# C-03_eMMC_NAND_TF_QSPI.net
KiCad netlist of a schematic drawn in Altium Designer
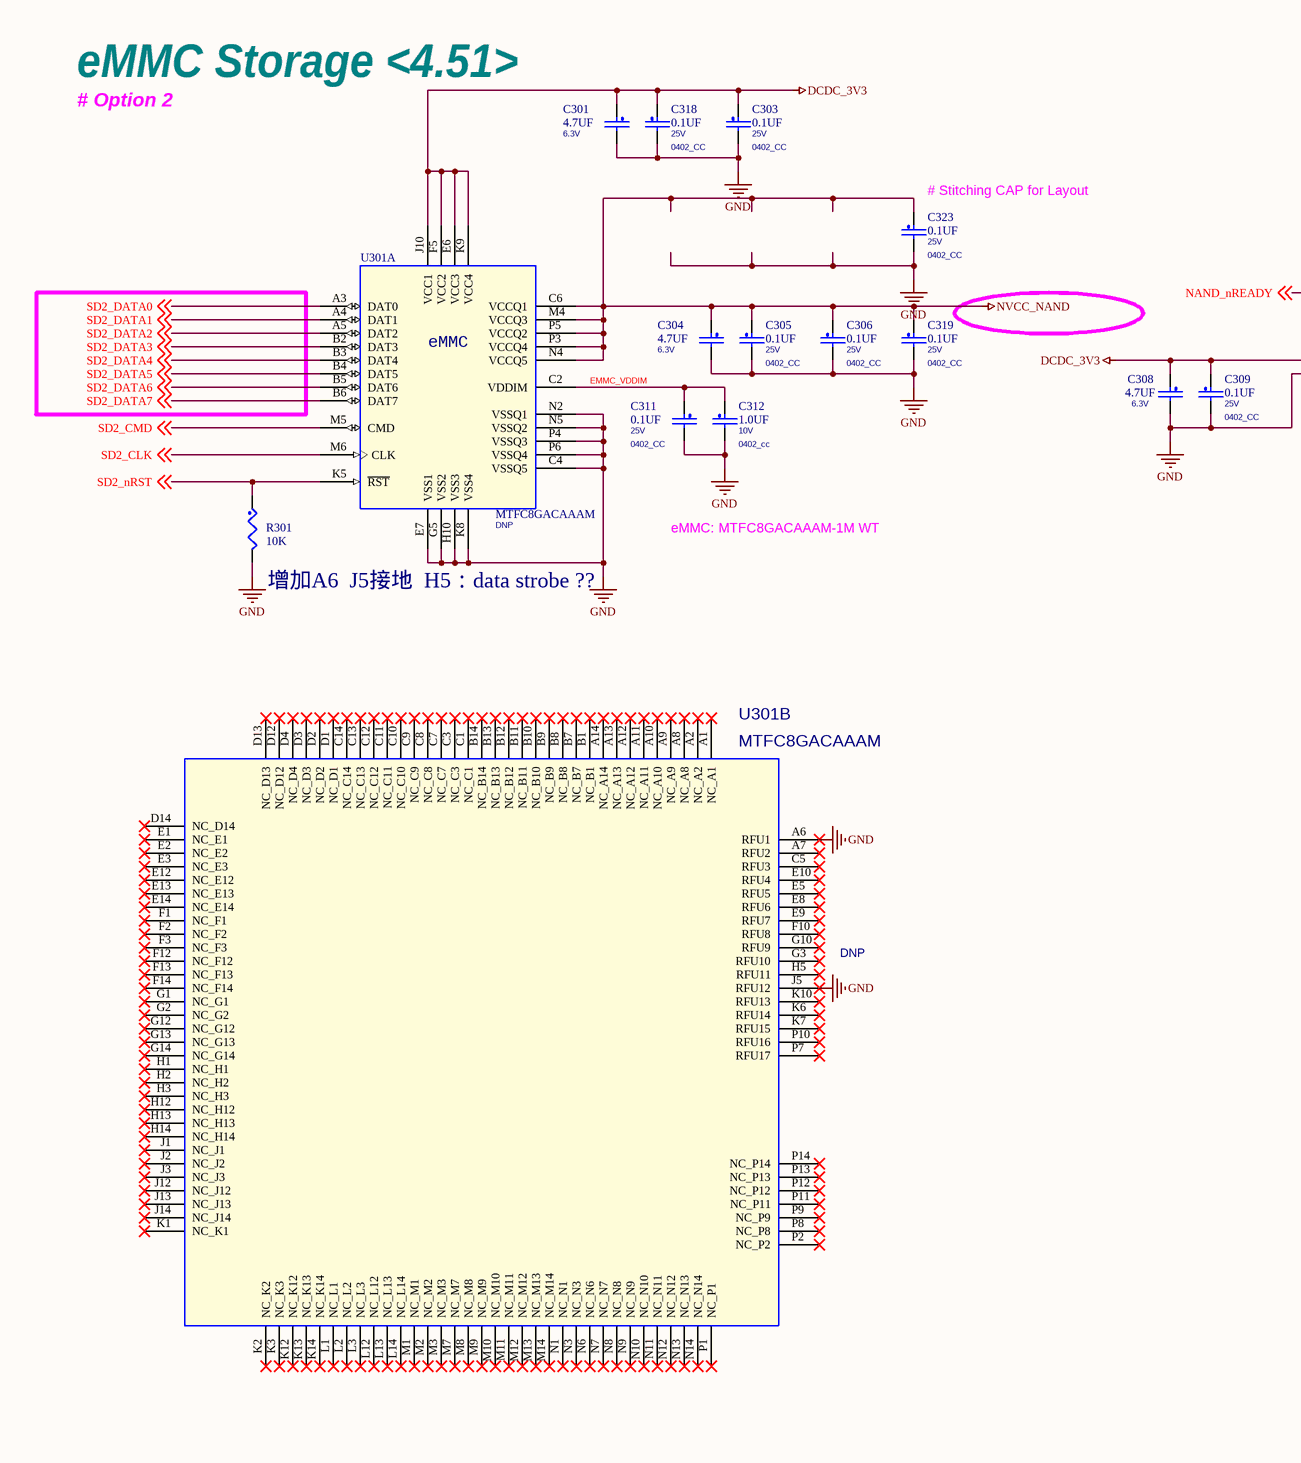
[diagram p0: C-03 eMMC_NAND_TF_QSPI.SchDoc, left]
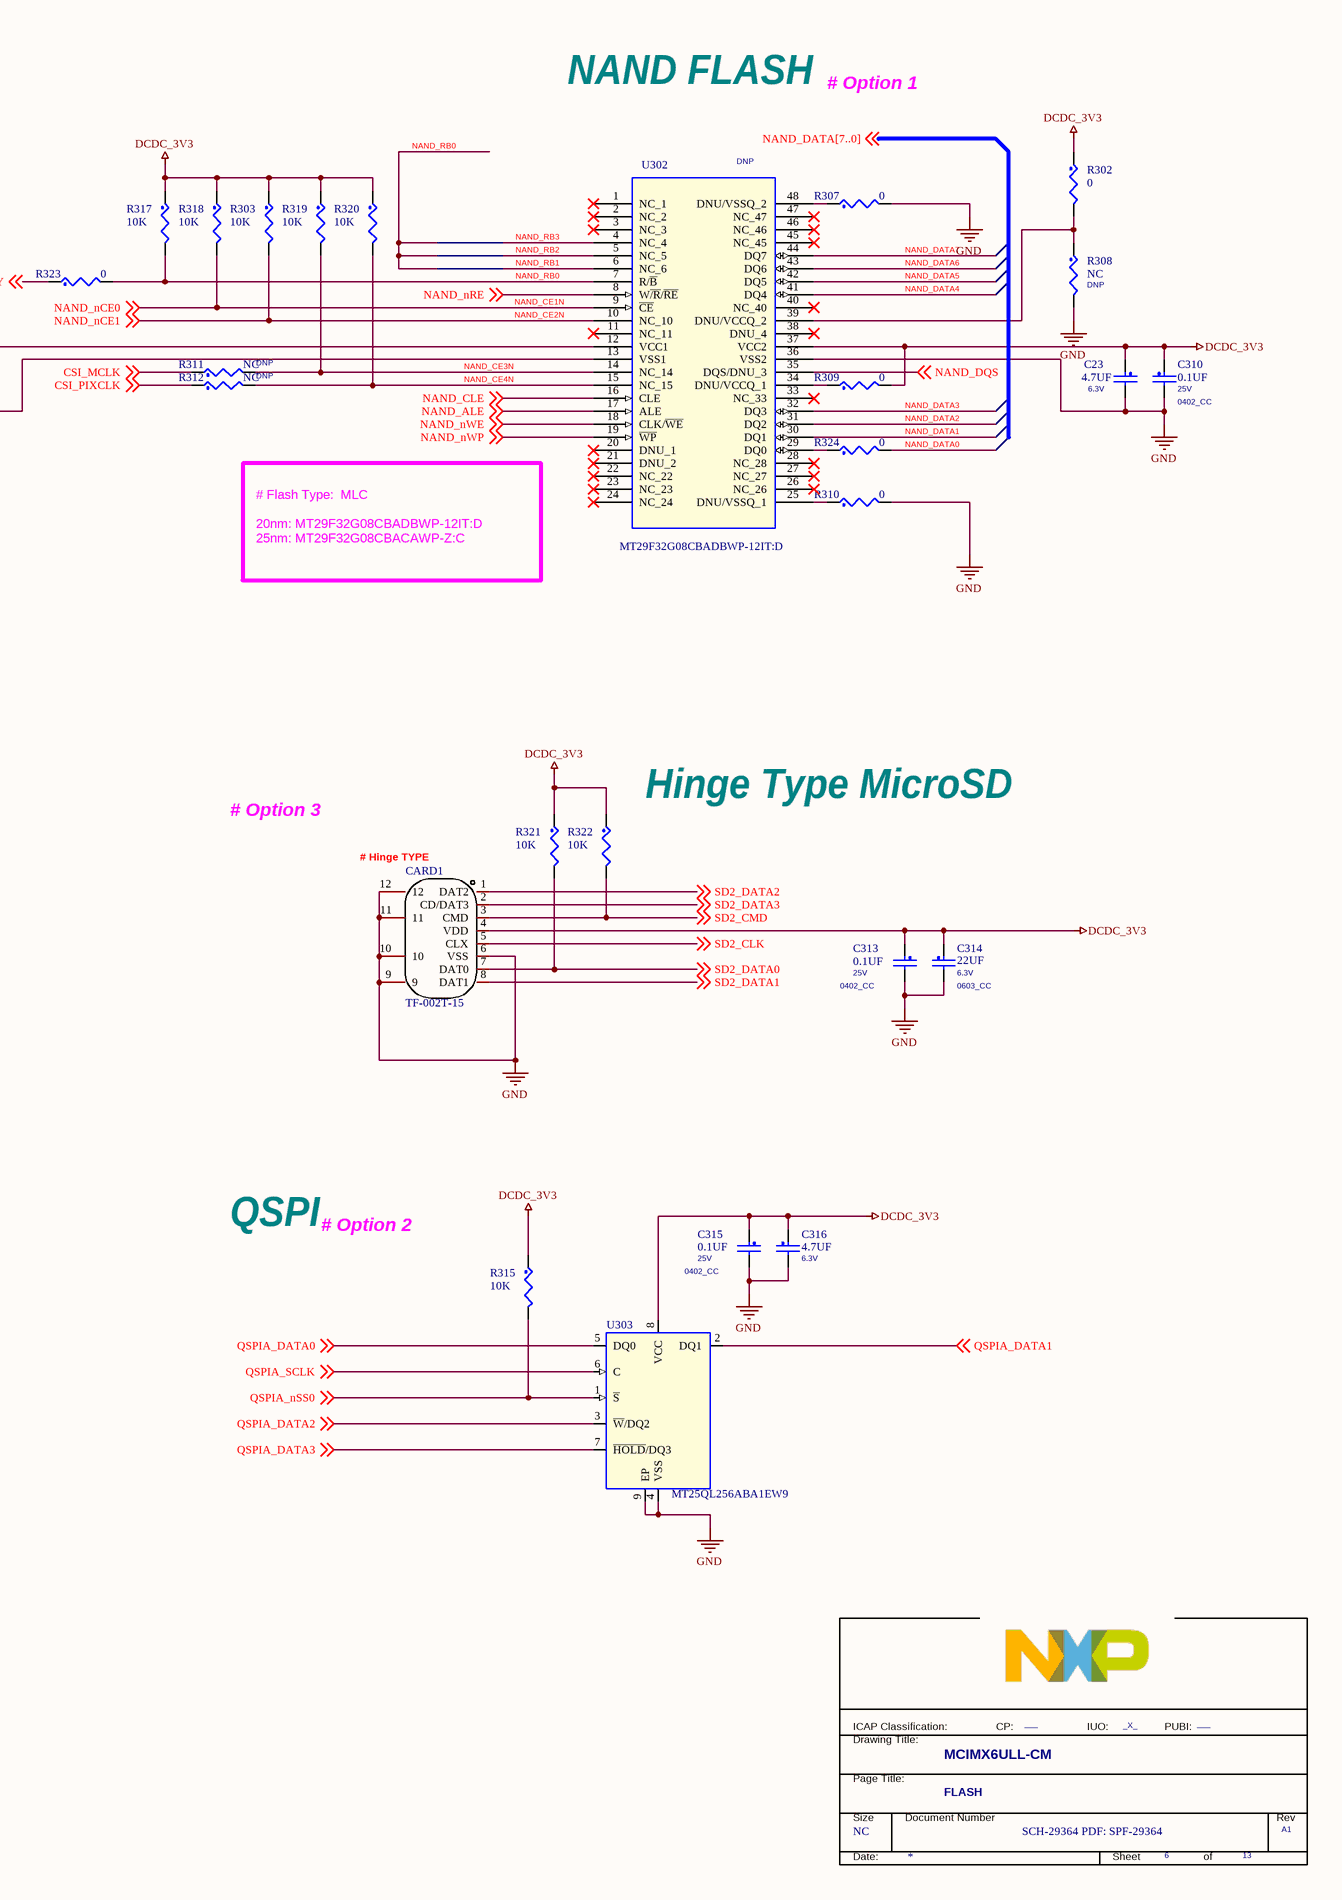
[diagram p1: C-03 eMMC_NAND_TF_QSPI.SchDoc, right]

(export (version "E")
  (design (tool "Eeschema 10.0.6"))
  (components
    (comp (ref "*")
      (value "TitleBlock_FS")
      (fields
        (field (name "PAGETITLE") "FLASH")
        (field (name "PAGE COUNT") "13")
        (field (name "PAGE NUMBER") "6")
        (field (name "PAGE SIZE") "NC")
        (field (name "TITLE") "MCIMX6ULL-CM")
        (field (name "REVCODE") "A1")
        (field (name "DOC") "SCH-29364 PDF: SPF-29364")
        (field (name "FCP") "___")
        (field (name "PUBI") "___")
        (field (name "FIUO") "_X_")
      )
      (libsource (lib "*") (part "TitleBlock_FS"))
    )
    (comp (ref "C23")
      (value "4.7UF")
      (footprint "0402T_C")
      (description "CAP CER 4.7UF 6.3V 20% X5R 0402")
      (fields
        (field (name "TOLERANCE") "20%")
        (field (name "VOLTAGE RATING") "6.3V")
        (field (name "VOLTAGE") "6.3V")
      )
      (libsource (lib "*") (part "CAP_NP"))
    )
    (comp (ref "C301")
      (value "4.7UF")
      (footprint "0402T_C")
      (description "CAP CER 4.7UF 6.3V 20% X5R 0402")
      (fields
        (field (name "TOLERANCE") "20%")
        (field (name "VOLTAGE RATING") "6.3V")
        (field (name "VOLTAGE") "6.3V")
      )
      (libsource (lib "*") (part "CAP_NP"))
    )
    (comp (ref "C303")
      (value "0.1UF")
      (footprint "0402T_C")
      (description "CAP CER 0.1UF 25V 10% X5R 0402")
      (fields
        (field (name "VOLTAGE") "25V")
        (field (name "TOLERANCE") "10%")
        (field (name "PCB FOOTPRINT") "0402_CC")
      )
      (libsource (lib "*") (part "CAP_NP"))
    )
    (comp (ref "C304")
      (value "4.7UF")
      (footprint "0402T_C")
      (description "CAP CER 4.7UF 6.3V 20% X5R 0402")
      (fields
        (field (name "VOLTAGE") "6.3V")
        (field (name "VOLTAGE RATING") "6.3V")
        (field (name "TOLERANCE") "20%")
      )
      (libsource (lib "*") (part "CAP_NP"))
    )
    (comp (ref "C305")
      (value "0.1UF")
      (footprint "0402T_C")
      (description "CAP CER 0.1UF 25V 10% X5R 0402")
      (fields
        (field (name "TOLERANCE") "10%")
        (field (name "VOLTAGE") "25V")
        (field (name "PCB FOOTPRINT") "0402_CC")
      )
      (libsource (lib "*") (part "CAP_NP"))
    )
    (comp (ref "C306")
      (value "0.1UF")
      (footprint "0402T_C")
      (description "CAP CER 0.1UF 25V 10% X5R 0402")
      (fields
        (field (name "TOLERANCE") "10%")
        (field (name "VOLTAGE") "25V")
        (field (name "PCB FOOTPRINT") "0402_CC")
      )
      (libsource (lib "*") (part "CAP_NP"))
    )
    (comp (ref "C308")
      (value "4.7UF")
      (footprint "0402T_C")
      (description "CAP CER 4.7UF 6.3V 20% X5R 0402")
      (fields
        (field (name "TOLERANCE") "20%")
        (field (name "VOLTAGE RATING") "6.3V")
        (field (name "VOLTAGE") "6.3V")
      )
      (libsource (lib "*") (part "CAP_NP"))
    )
    (comp (ref "C309")
      (value "0.1UF")
      (footprint "0402T_C")
      (description "CAP CER 0.1UF 25V 10% X5R 0402")
      (fields
        (field (name "TOLERANCE") "10%")
        (field (name "VOLTAGE") "25V")
        (field (name "PCB FOOTPRINT") "0402_CC")
      )
      (libsource (lib "*") (part "CAP_NP"))
    )
    (comp (ref "C310")
      (value "0.1UF")
      (footprint "0402T_C")
      (description "CAP CER 0.1UF 25V 10% X5R 0402")
      (fields
        (field (name "VOLTAGE") "25V")
        (field (name "TOLERANCE") "10%")
        (field (name "PCB FOOTPRINT") "0402_CC")
      )
      (libsource (lib "*") (part "CAP_NP"))
    )
    (comp (ref "C311")
      (value "0.1UF")
      (footprint "0402T_C")
      (description "CAP CER 0.1UF 25V 10% X5R 0402")
      (fields
        (field (name "TOLERANCE") "10%")
        (field (name "VOLTAGE") "25V")
        (field (name "PCB FOOTPRINT") "0402_CC")
      )
      (libsource (lib "*") (part "CAP_NP"))
    )
    (comp (ref "C312")
      (value "1.0UF")
      (footprint "0402T_C")
      (description "CAP CER 1.0UF 10V 10% X5R 0402")
      (fields (field (name "VOLTAGE") "10V") (field (name "PCB FOOTPRINT") "0402_cc"))
      (libsource (lib "*") (part "CAP_NP"))
    )
    (comp (ref "C313")
      (value "0.1UF")
      (footprint "0402T_C")
      (description "CAP CER 0.1UF 25V 10% X5R 0402")
      (fields
        (field (name "TOLERANCE") "10%")
        (field (name "VOLTAGE") "25V")
        (field (name "PCB FOOTPRINT") "0402_CC")
      )
      (libsource (lib "*") (part "CAP_NP"))
    )
    (comp (ref "C314")
      (value "22UF")
      (footprint "0603_CC")
      (description "CAP CER 22UF 6.3V 20% X5R 0603")
      (fields
        (field (name "VOLTAGE RATING") "6.3V")
        (field (name "TOLERANCE") "20%")
        (field (name "VOLTAGE") "6.3V")
        (field (name "PCB FOOTPRINT") "0603_CC")
      )
      (libsource (lib "*") (part "CAP_NP"))
    )
    (comp (ref "C315")
      (value "0.1UF")
      (footprint "0402T_C")
      (description "CAP CER 0.1UF 25V 10% X5R 0402")
      (fields
        (field (name "TOLERANCE") "10%")
        (field (name "VOLTAGE") "25V")
        (field (name "PCB FOOTPRINT") "0402_CC")
      )
      (libsource (lib "*") (part "CAP_NP"))
    )
    (comp (ref "C316")
      (value "4.7UF")
      (footprint "0402T_C")
      (description "CAP CER 4.7UF 6.3V 20% X5R 0402")
      (fields
        (field (name "TOLERANCE") "20%")
        (field (name "VOLTAGE RATING") "6.3V")
        (field (name "VOLTAGE") "6.3V")
      )
      (libsource (lib "*") (part "CAP_NP"))
    )
    (comp (ref "C318")
      (value "0.1UF")
      (footprint "0402T_C")
      (description "CAP CER 0.1UF 25V 10% X5R 0402")
      (fields
        (field (name "TOLERANCE") "10%")
        (field (name "VOLTAGE") "25V")
        (field (name "PCB FOOTPRINT") "0402_CC")
      )
      (libsource (lib "*") (part "CAP_NP"))
    )
    (comp (ref "C319")
      (value "0.1UF")
      (footprint "0402T_C")
      (description "CAP CER 0.1UF 25V 10% X5R 0402")
      (fields
        (field (name "VOLTAGE") "25V")
        (field (name "TOLERANCE") "10%")
        (field (name "PCB FOOTPRINT") "0402_CC")
      )
      (libsource (lib "*") (part "CAP_NP"))
    )
    (comp (ref "C323")
      (value "0.1UF")
      (footprint "0402T_C")
      (description "CAP CER 0.1UF 25V 10% X5R 0402")
      (fields
        (field (name "TOLERANCE") "10%")
        (field (name "VOLTAGE") "25V")
        (field (name "PCB FOOTPRINT") "0402_CC")
      )
      (libsource (lib "*") (part "CAP_NP"))
    )
    (comp (ref "CARD1")
      (value "TF-002T-15")
      (footprint "TF-SMD_TF-002T-15")
      (description "卡连接方式:翻盖式;卡类型:MicroSD卡(TF卡);连接器类型:卡座;本体最大高度:-;触头材质:-;触头镀层:-;工作温度范围:-;焊接温度(最大值):-;")
      (fields (field (name "NAME") "TF-002T-15") (field (name "MANUFACTURER") "SOFNG(硕方)"))
      (libsource (lib "altium-import") (part "root_0_mirrored_TF-002T-15_"))
    )
    (comp (ref "R301")
      (value "10K")
      (footprint "0402T_C")
      (description "RES MF 10K 1/16W 5% 0402")
      (fields (field (name "TOLERANCE") "5%"))
      (libsource (lib "*") (part "RES"))
    )
    (comp (ref "R302")
      (value "0")
      (footprint "0402T_C")
      (description "RES MF ZERO OHM 1/16W 5% 0402")
      (fields (field (name "TOLERANCE") "5%"))
      (libsource (lib "*") (part "RES"))
    )
    (comp (ref "R303")
      (value "10K")
      (footprint "0402T_C")
      (description "RES MF 10K 1/16W 5% 0402")
      (fields (field (name "TOLERANCE") "5%"))
      (libsource (lib "*") (part "RES"))
    )
    (comp (ref "R307")
      (value "0")
      (footprint "0402T_C")
      (description "RES MF ZERO OHM 1/16W 5% 0402")
      (fields (field (name "TOLERANCE") "5%"))
      (libsource (lib "*") (part "RES"))
    )
    (comp (ref "R308")
      (value "NC")
      (footprint "0402T_C")
      (description "RES MF ZERO OHM 1/16W 5% 0402")
      (fields (field (name "ASSY_OPT") "DNP") (field (name "TOLERANCE") "5%"))
      (libsource (lib "*") (part "RES"))
    )
    (comp (ref "R309")
      (value "0")
      (footprint "0402T_C")
      (description "RES MF ZERO OHM 1/16W 5% 0402")
      (fields (field (name "TOLERANCE") "5%"))
      (libsource (lib "*") (part "RES"))
    )
    (comp (ref "R310")
      (value "0")
      (footprint "0402T_C")
      (description "RES MF ZERO OHM 1/16W 5% 0402")
      (fields (field (name "TOLERANCE") "5%"))
      (libsource (lib "*") (part "RES"))
    )
    (comp (ref "R311")
      (value "NC")
      (footprint "0402T_C")
      (description "RES MF ZERO OHM 1/16W 5% 0402")
      (fields (field (name "ASSY_OPT") "DNP") (field (name "TOLERANCE") "5%"))
      (libsource (lib "*") (part "RES"))
    )
    (comp (ref "R312")
      (value "NC")
      (footprint "0402T_C")
      (description "RES MF ZERO OHM 1/16W 5% 0402")
      (fields (field (name "ASSY_OPT") "DNP") (field (name "TOLERANCE") "5%"))
      (libsource (lib "*") (part "RES"))
    )
    (comp (ref "R315")
      (value "10K")
      (footprint "0402T_C")
      (description "RES MF 10K 1/16W 5% 0402")
      (fields (field (name "TOLERANCE") "5%"))
      (libsource (lib "*") (part "RES"))
    )
    (comp (ref "R317")
      (value "10K")
      (footprint "0402T_C")
      (description "RES MF 10K 1/16W 5% 0402")
      (fields (field (name "TOLERANCE") "5%"))
      (libsource (lib "*") (part "RES"))
    )
    (comp (ref "R318")
      (value "10K")
      (footprint "0402T_C")
      (description "RES MF 10K 1/16W 5% 0402")
      (fields (field (name "TOLERANCE") "5%"))
      (libsource (lib "*") (part "RES"))
    )
    (comp (ref "R319")
      (value "10K")
      (footprint "0402T_C")
      (description "RES MF 10K 1/16W 5% 0402")
      (fields (field (name "TOLERANCE") "5%"))
      (libsource (lib "*") (part "RES"))
    )
    (comp (ref "R320")
      (value "10K")
      (footprint "0402T_C")
      (description "RES MF 10K 1/16W 5% 0402")
      (fields (field (name "TOLERANCE") "5%"))
      (libsource (lib "*") (part "RES"))
    )
    (comp (ref "R321")
      (value "10K")
      (footprint "0402T_C")
      (description "RES MF 10K 1/16W 5% 0402")
      (fields (field (name "TOLERANCE") "5%"))
      (libsource (lib "*") (part "RES"))
    )
    (comp (ref "R322")
      (value "10K")
      (footprint "0402T_C")
      (description "RES MF 10K 1/16W 5% 0402")
      (fields (field (name "TOLERANCE") "5%"))
      (libsource (lib "*") (part "RES"))
    )
    (comp (ref "R323")
      (value "0")
      (footprint "0402T_C")
      (description "RES MF ZERO OHM 1/16W 5% 0402")
      (fields (field (name "TOLERANCE") "5%"))
      (libsource (lib "*") (part "RES"))
    )
    (comp (ref "R324")
      (value "0")
      (footprint "0402T_C")
      (description "RES MF ZERO OHM 1/16W 5% 0402")
      (fields (field (name "TOLERANCE") "5%"))
      (libsource (lib "*") (part "RES"))
    )
    (comp (ref "U301")
      (value "MTFC8GACAAAM")
      (footprint "FBGA153_0P5_11P5X13")
      (description "IC MEM NAND FLASH 8GB MMC 4.51 CTLR 2.7-3.6V FBGA153")
      (fields (field (name "ASSY_OPT") "DNP"))
      (libsource (lib "*") (part "MTFC4GMVEA_WFBGA_153P"))
    )
    (comp (ref "U302")
      (value "MT29F32G08CBADBWP-12IT:D")
      (footprint "tsop48_12x20")
      (description "IC MEM NAND FLASH ASYNC 32GB 2.7-3.6V TSOP48")
      (fields (field (name "ASSY_OPT") "DNP"))
      (libsource (lib "*") (part "MT29F32G08CBADB_48P"))
    )
    (comp (ref "U303")
      (value "MT25QL256ABA1EW9")
      (footprint "mlp8_1p27_8x6")
      (description "IC MEM FLASH SERIAL NOR 256MBIT 2.7-3.6V MLP8")
      (libsource (lib "*") (part "MT25QL256ABA1EW9_9P"))
    )
  )
  (nets
    (net (code "1") (name "/EMMC_VDDIM") (class "Default")
      (node (ref "C311") (pin "1") (pinfunction "1_1") (pintype "passive"))
      (node (ref "C312") (pin "1") (pinfunction "1_1") (pintype "passive"))
      (node (ref "U301") (pin "C2") (pinfunction "VDDIM_C2") (pintype "power_in"))
    )
    (net (code "2") (name "/NAND_CE3N") (class "Default")
      (node (ref "R311") (pin "2") (pinfunction "2_2") (pintype "passive"))
      (node (ref "R319") (pin "2") (pinfunction "2_2") (pintype "passive"))
      (node (ref "U302") (pin "14") (pinfunction "NC_14_14") (pintype "passive"))
    )
    (net (code "3") (name "/NAND_CE4N") (class "Default")
      (node (ref "R312") (pin "2") (pinfunction "2_2") (pintype "passive"))
      (node (ref "R320") (pin "2") (pinfunction "2_2") (pintype "passive"))
      (node (ref "U302") (pin "15") (pinfunction "NC_15_15") (pintype "passive"))
    )
    (net (code "4") (name "/NAND_RB0") (class "Default")
      (node (ref "R317") (pin "2") (pinfunction "2_2") (pintype "passive"))
      (node (ref "R323") (pin "2") (pinfunction "2_2") (pintype "passive"))
      (node (ref "U302") (pin "4") (pinfunction "NC_4_4") (pintype "passive"))
      (node (ref "U302") (pin "5") (pinfunction "NC_5_5") (pintype "passive"))
      (node (ref "U302") (pin "6") (pinfunction "NC_6_6") (pintype "passive"))
      (node (ref "U302") (pin "7") (pinfunction "R/~{B}_7") (pintype "open_collector"))
    )
    (net (code "5") (name "CSI_MCLK") (class "Default")
      (node (ref "R311") (pin "1") (pinfunction "1_1") (pintype "passive"))
    )
    (net (code "6") (name "CSI_PIXCLK") (class "Default")
      (node (ref "R312") (pin "1") (pinfunction "1_1") (pintype "passive"))
    )
    (net (code "7") (name "DCDC_3V3") (class "Default")
      (node (ref "C23") (pin "1") (pinfunction "1_1") (pintype "passive"))
      (node (ref "C301") (pin "1") (pinfunction "1_1") (pintype "passive"))
      (node (ref "C303") (pin "1") (pinfunction "1_1") (pintype "passive"))
      (node (ref "C308") (pin "1") (pinfunction "1_1") (pintype "passive"))
      (node (ref "C309") (pin "1") (pinfunction "1_1") (pintype "passive"))
      (node (ref "C310") (pin "1") (pinfunction "1_1") (pintype "passive"))
      (node (ref "C313") (pin "1") (pinfunction "1_1") (pintype "passive"))
      (node (ref "C314") (pin "1") (pinfunction "1_1") (pintype "passive"))
      (node (ref "C315") (pin "1") (pinfunction "1_1") (pintype "passive"))
      (node (ref "C316") (pin "1") (pinfunction "1_1") (pintype "passive"))
      (node (ref "C318") (pin "1") (pinfunction "1_1") (pintype "passive"))
      (node (ref "CARD1") (pin "4") (pinfunction "VDD_4") (pintype "passive"))
      (node (ref "R302") (pin "1") (pinfunction "1_1") (pintype "passive"))
      (node (ref "R303") (pin "1") (pinfunction "1_1") (pintype "passive"))
      (node (ref "R309") (pin "2") (pinfunction "2_2") (pintype "passive"))
      (node (ref "R315") (pin "1") (pinfunction "1_1") (pintype "passive"))
      (node (ref "R317") (pin "1") (pinfunction "1_1") (pintype "passive"))
      (node (ref "R318") (pin "1") (pinfunction "1_1") (pintype "passive"))
      (node (ref "R319") (pin "1") (pinfunction "1_1") (pintype "passive"))
      (node (ref "R320") (pin "1") (pinfunction "1_1") (pintype "passive"))
      (node (ref "R321") (pin "1") (pinfunction "1_1") (pintype "passive"))
      (node (ref "R322") (pin "1") (pinfunction "1_1") (pintype "passive"))
      (node (ref "U301") (pin "E6") (pinfunction "VCC3_E6") (pintype "power_in"))
      (node (ref "U301") (pin "F5") (pinfunction "VCC2_F5") (pintype "power_in"))
      (node (ref "U301") (pin "J10") (pinfunction "VCC1_J10") (pintype "power_in"))
      (node (ref "U301") (pin "K9") (pinfunction "VCC4_K9") (pintype "power_in"))
      (node (ref "U302") (pin "12") (pinfunction "VCC1_12") (pintype "power_in"))
      (node (ref "U302") (pin "37") (pinfunction "VCC2_37") (pintype "power_in"))
      (node (ref "U303") (pin "8") (pinfunction "VCC_8") (pintype "power_in"))
    )
    (net (code "8") (name "GND") (class "Default")
      (node (ref "C23") (pin "2") (pinfunction "2_2") (pintype "passive"))
      (node (ref "C301") (pin "2") (pinfunction "2_2") (pintype "passive"))
      (node (ref "C303") (pin "2") (pinfunction "2_2") (pintype "passive"))
      (node (ref "C304") (pin "2") (pinfunction "2_2") (pintype "passive"))
      (node (ref "C305") (pin "2") (pinfunction "2_2") (pintype "passive"))
      (node (ref "C306") (pin "2") (pinfunction "2_2") (pintype "passive"))
      (node (ref "C308") (pin "2") (pinfunction "2_2") (pintype "passive"))
      (node (ref "C309") (pin "2") (pinfunction "2_2") (pintype "passive"))
      (node (ref "C310") (pin "2") (pinfunction "2_2") (pintype "passive"))
      (node (ref "C311") (pin "2") (pinfunction "2_2") (pintype "passive"))
      (node (ref "C312") (pin "2") (pinfunction "2_2") (pintype "passive"))
      (node (ref "C313") (pin "2") (pinfunction "2_2") (pintype "passive"))
      (node (ref "C314") (pin "2") (pinfunction "2_2") (pintype "passive"))
      (node (ref "C315") (pin "2") (pinfunction "2_2") (pintype "passive"))
      (node (ref "C316") (pin "2") (pinfunction "2_2") (pintype "passive"))
      (node (ref "C318") (pin "2") (pinfunction "2_2") (pintype "passive"))
      (node (ref "C319") (pin "2") (pinfunction "2_2") (pintype "passive"))
      (node (ref "C323") (pin "2") (pinfunction "2_2") (pintype "passive"))
      (node (ref "CARD1") (pin "10") (pinfunction "10_10") (pintype "passive"))
      (node (ref "CARD1") (pin "11") (pinfunction "11_11") (pintype "passive"))
      (node (ref "CARD1") (pin "12") (pinfunction "12_12") (pintype "passive"))
      (node (ref "CARD1") (pin "6") (pinfunction "VSS_6") (pintype "passive"))
      (node (ref "CARD1") (pin "9") (pinfunction "9_9") (pintype "passive"))
      (node (ref "R301") (pin "2") (pinfunction "2_2") (pintype "passive"))
      (node (ref "R307") (pin "2") (pinfunction "2_2") (pintype "passive"))
      (node (ref "R308") (pin "2") (pinfunction "2_2") (pintype "passive"))
      (node (ref "R310") (pin "2") (pinfunction "2_2") (pintype "passive"))
      (node (ref "U301") (pin "A6") (pinfunction "RFU1_A6") (pintype "passive"))
      (node (ref "U301") (pin "C4") (pinfunction "VSSQ5_C4") (pintype "power_in"))
      (node (ref "U301") (pin "E7") (pinfunction "VSS1_E7") (pintype "power_in"))
      (node (ref "U301") (pin "G5") (pinfunction "VSS2_G5") (pintype "power_in"))
      (node (ref "U301") (pin "H10") (pinfunction "VSS3_H10") (pintype "power_in"))
      (node (ref "U301") (pin "J5") (pinfunction "RFU12_J5") (pintype "passive"))
      (node (ref "U301") (pin "K8") (pinfunction "VSS4_K8") (pintype "power_in"))
      (node (ref "U301") (pin "N2") (pinfunction "VSSQ1_N2") (pintype "power_in"))
      (node (ref "U301") (pin "N5") (pinfunction "VSSQ2_N5") (pintype "power_in"))
      (node (ref "U301") (pin "P4") (pinfunction "VSSQ3_P4") (pintype "power_in"))
      (node (ref "U301") (pin "P6") (pinfunction "VSSQ4_P6") (pintype "power_in"))
      (node (ref "U302") (pin "13") (pinfunction "VSS1_13") (pintype "power_in"))
      (node (ref "U302") (pin "36") (pinfunction "VSS2_36") (pintype "power_in"))
      (node (ref "U303") (pin "4") (pinfunction "VSS_4") (pintype "power_in"))
      (node (ref "U303") (pin "9") (pinfunction "EP_9") (pintype "power_in"))
    )
    (net (code "9") (name "NAND_ALE") (class "Default")
      (node (ref "U302") (pin "17") (pinfunction "ALE_17") (pintype "input"))
    )
    (net (code "10") (name "NAND_CLE") (class "Default")
      (node (ref "U302") (pin "16") (pinfunction "CLE_16") (pintype "input"))
    )
    (net (code "11") (name "NAND_DATA0") (class "Default")
      (node (ref "R324") (pin "2") (pinfunction "2_2") (pintype "passive"))
    )
    (net (code "12") (name "NAND_DATA1") (class "Default")
      (node (ref "U302") (pin "30") (pinfunction "DQ1_30") (pintype "bidirectional"))
    )
    (net (code "13") (name "NAND_DATA2") (class "Default")
      (node (ref "U302") (pin "31") (pinfunction "DQ2_31") (pintype "bidirectional"))
    )
    (net (code "14") (name "NAND_DATA3") (class "Default")
      (node (ref "U302") (pin "32") (pinfunction "DQ3_32") (pintype "bidirectional"))
    )
    (net (code "15") (name "NAND_DATA4") (class "Default")
      (node (ref "U302") (pin "41") (pinfunction "DQ4_41") (pintype "bidirectional"))
    )
    (net (code "16") (name "NAND_DATA5") (class "Default")
      (node (ref "U302") (pin "42") (pinfunction "DQ5_42") (pintype "bidirectional"))
    )
    (net (code "17") (name "NAND_DATA6") (class "Default")
      (node (ref "U302") (pin "43") (pinfunction "DQ6_43") (pintype "bidirectional"))
    )
    (net (code "18") (name "NAND_DATA7") (class "Default")
      (node (ref "U302") (pin "44") (pinfunction "DQ7_44") (pintype "bidirectional"))
    )
    (net (code "20") (name "NAND_DQS") (class "Default")
      (node (ref "U302") (pin "35") (pinfunction "DQS/DNU_3_35") (pintype "passive"))
    )
    (net (code "21") (name "NAND_nCE0") (class "Default")
      (node (ref "R318") (pin "2") (pinfunction "2_2") (pintype "passive"))
      (node (ref "U302") (pin "9") (pinfunction "~{CE}_9") (pintype "input"))
    )
    (net (code "22") (name "NAND_nCE1") (class "Default")
      (node (ref "R303") (pin "2") (pinfunction "2_2") (pintype "passive"))
      (node (ref "U302") (pin "10") (pinfunction "NC_10_10") (pintype "passive"))
    )
    (net (code "23") (name "NAND_nRE") (class "Default")
      (node (ref "U302") (pin "8") (pinfunction "W~{/R}/~{RE}_8") (pintype "input"))
    )
    (net (code "24") (name "NAND_nREADY") (class "Default")
      (node (ref "R323") (pin "1") (pinfunction "1_1") (pintype "passive"))
    )
    (net (code "25") (name "NAND_nWE") (class "Default")
      (node (ref "U302") (pin "18") (pinfunction "CLK/~{WE}_18") (pintype "input"))
    )
    (net (code "26") (name "NAND_nWP") (class "Default")
      (node (ref "U302") (pin "19") (pinfunction "~{WP}_19") (pintype "input"))
    )
    (net (code "27") (name "NVCC_NAND") (class "Default")
      (node (ref "C304") (pin "1") (pinfunction "1_1") (pintype "passive"))
      (node (ref "C305") (pin "1") (pinfunction "1_1") (pintype "passive"))
      (node (ref "C306") (pin "1") (pinfunction "1_1") (pintype "passive"))
      (node (ref "C319") (pin "1") (pinfunction "1_1") (pintype "passive"))
      (node (ref "C323") (pin "1") (pinfunction "1_1") (pintype "passive"))
      (node (ref "U301") (pin "C6") (pinfunction "VCCQ1_C6") (pintype "power_in"))
      (node (ref "U301") (pin "M4") (pinfunction "VCCQ3_M4") (pintype "power_in"))
      (node (ref "U301") (pin "N4") (pinfunction "VCCQ5_N4") (pintype "power_in"))
      (node (ref "U301") (pin "P3") (pinfunction "VCCQ4_P3") (pintype "power_in"))
      (node (ref "U301") (pin "P5") (pinfunction "VCCQ2_P5") (pintype "power_in"))
    )
    (net (code "28") (name "Net-(U302-DNU{slash}VCCQ_1)") (class "Default")
      (node (ref "R309") (pin "1") (pinfunction "1_1") (pintype "passive"))
      (node (ref "U302") (pin "34") (pinfunction "DNU/VCCQ_1_34") (pintype "power_in"))
    )
    (net (code "29") (name "Net-(U302-DNU{slash}VCCQ_2)") (class "Default")
      (node (ref "R302") (pin "2") (pinfunction "2_2") (pintype "passive"))
      (node (ref "R308") (pin "1") (pinfunction "1_1") (pintype "passive"))
      (node (ref "U302") (pin "39") (pinfunction "DNU/VCCQ_2_39") (pintype "passive"))
    )
    (net (code "30") (name "Net-(U302-DNU{slash}VSSQ_1)") (class "Default")
      (node (ref "R310") (pin "1") (pinfunction "1_1") (pintype "passive"))
      (node (ref "U302") (pin "25") (pinfunction "DNU/VSSQ_1_25") (pintype "power_in"))
    )
    (net (code "31") (name "Net-(U302-DNU{slash}VSSQ_2)") (class "Default")
      (node (ref "R307") (pin "1") (pinfunction "1_1") (pintype "passive"))
      (node (ref "U302") (pin "48") (pinfunction "DNU/VSSQ_2_48") (pintype "power_in"))
    )
    (net (code "32") (name "Net-(U302-DQ0)") (class "Default")
      (node (ref "R324") (pin "1") (pinfunction "1_1") (pintype "passive"))
      (node (ref "U302") (pin "29") (pinfunction "DQ0_29") (pintype "bidirectional"))
    )
    (net (code "33") (name "QSPIA_DATA0") (class "Default")
      (node (ref "U303") (pin "5") (pinfunction "DQ0_5") (pintype "bidirectional"))
    )
    (net (code "34") (name "QSPIA_DATA1") (class "Default")
      (node (ref "U303") (pin "2") (pinfunction "DQ1_2") (pintype "bidirectional"))
    )
    (net (code "35") (name "QSPIA_DATA2") (class "Default")
      (node (ref "U303") (pin "3") (pinfunction "~{W}/DQ2_3") (pintype "bidirectional"))
    )
    (net (code "36") (name "QSPIA_DATA3") (class "Default")
      (node (ref "U303") (pin "7") (pinfunction "~{HOLD}/DQ3_7") (pintype "bidirectional"))
    )
    (net (code "37") (name "QSPIA_SCLK") (class "Default")
      (node (ref "U303") (pin "6") (pinfunction "C_6") (pintype "input"))
    )
    (net (code "38") (name "QSPIA_nSS0") (class "Default")
      (node (ref "R315") (pin "2") (pinfunction "2_2") (pintype "passive"))
      (node (ref "U303") (pin "1") (pinfunction "~{S}_1") (pintype "input"))
    )
    (net (code "39") (name "SD2_CLK") (class "Default")
      (node (ref "CARD1") (pin "5") (pinfunction "CLX_5") (pintype "passive"))
      (node (ref "U301") (pin "M6") (pinfunction "CLK_M6") (pintype "input"))
    )
    (net (code "40") (name "SD2_CMD") (class "Default")
      (node (ref "CARD1") (pin "3") (pinfunction "CMD_3") (pintype "passive"))
      (node (ref "R322") (pin "2") (pinfunction "2_2") (pintype "passive"))
      (node (ref "U301") (pin "M5") (pinfunction "CMD_M5") (pintype "bidirectional"))
    )
    (net (code "41") (name "SD2_DATA0") (class "Default")
      (node (ref "CARD1") (pin "7") (pinfunction "DAT0_7") (pintype "passive"))
      (node (ref "R321") (pin "2") (pinfunction "2_2") (pintype "passive"))
      (node (ref "U301") (pin "A3") (pinfunction "DAT0_A3") (pintype "bidirectional"))
    )
    (net (code "42") (name "SD2_DATA1") (class "Default")
      (node (ref "CARD1") (pin "8") (pinfunction "DAT1_8") (pintype "passive"))
      (node (ref "U301") (pin "A4") (pinfunction "DAT1_A4") (pintype "bidirectional"))
    )
    (net (code "43") (name "SD2_DATA2") (class "Default")
      (node (ref "CARD1") (pin "1") (pinfunction "DAT2_1") (pintype "passive"))
      (node (ref "U301") (pin "A5") (pinfunction "DAT2_A5") (pintype "bidirectional"))
    )
    (net (code "44") (name "SD2_DATA3") (class "Default")
      (node (ref "CARD1") (pin "2") (pinfunction "CD/DAT3_2") (pintype "passive"))
      (node (ref "U301") (pin "B2") (pinfunction "DAT3_B2") (pintype "bidirectional"))
    )
    (net (code "45") (name "SD2_DATA4") (class "Default")
      (node (ref "U301") (pin "B3") (pinfunction "DAT4_B3") (pintype "bidirectional"))
    )
    (net (code "46") (name "SD2_DATA5") (class "Default")
      (node (ref "U301") (pin "B4") (pinfunction "DAT5_B4") (pintype "bidirectional"))
    )
    (net (code "47") (name "SD2_DATA6") (class "Default")
      (node (ref "U301") (pin "B5") (pinfunction "DAT6_B5") (pintype "bidirectional"))
    )
    (net (code "48") (name "SD2_DATA7") (class "Default")
      (node (ref "U301") (pin "B6") (pinfunction "DAT7_B6") (pintype "bidirectional"))
    )
    (net (code "49") (name "SD2_nRST") (class "Default")
      (node (ref "R301") (pin "1") (pinfunction "1_1") (pintype "passive"))
      (node (ref "U301") (pin "K5") (pinfunction "~{RST}_K5") (pintype "input"))
    )
    (net (code "50") (name "unconnected-(U301B-NC_A1-PadA1)") (class "Default")
      (node (ref "U301") (pin "A1") (pinfunction "NC_A1_A1") (pintype "passive+no_connect"))
    )
    (net (code "51") (name "unconnected-(U301B-NC_A2-PadA2)") (class "Default")
      (node (ref "U301") (pin "A2") (pinfunction "NC_A2_A2") (pintype "passive+no_connect"))
    )
    (net (code "52") (name "unconnected-(U301B-NC_A8-PadA8)") (class "Default")
      (node (ref "U301") (pin "A8") (pinfunction "NC_A8_A8") (pintype "passive+no_connect"))
    )
    (net (code "53") (name "unconnected-(U301B-NC_A9-PadA9)") (class "Default")
      (node (ref "U301") (pin "A9") (pinfunction "NC_A9_A9") (pintype "passive+no_connect"))
    )
    (net (code "54") (name "unconnected-(U301B-NC_A10-PadA10)") (class "Default")
      (node (ref "U301") (pin "A10") (pinfunction "NC_A10_A10") (pintype "passive+no_connect"))
    )
    (net (code "55") (name "unconnected-(U301B-NC_A11-PadA11)") (class "Default")
      (node (ref "U301") (pin "A11") (pinfunction "NC_A11_A11") (pintype "passive+no_connect"))
    )
    (net (code "56") (name "unconnected-(U301B-NC_A12-PadA12)") (class "Default")
      (node (ref "U301") (pin "A12") (pinfunction "NC_A12_A12") (pintype "passive+no_connect"))
    )
    (net (code "57") (name "unconnected-(U301B-NC_A13-PadA13)") (class "Default")
      (node (ref "U301") (pin "A13") (pinfunction "NC_A13_A13") (pintype "passive+no_connect"))
    )
    (net (code "58") (name "unconnected-(U301B-NC_A14-PadA14)") (class "Default")
      (node (ref "U301") (pin "A14") (pinfunction "NC_A14_A14") (pintype "passive+no_connect"))
    )
    (net (code "59") (name "unconnected-(U301B-NC_B1-PadB1)") (class "Default")
      (node (ref "U301") (pin "B1") (pinfunction "NC_B1_B1") (pintype "passive+no_connect"))
    )
    (net (code "60") (name "unconnected-(U301B-NC_B7-PadB7)") (class "Default")
      (node (ref "U301") (pin "B7") (pinfunction "NC_B7_B7") (pintype "passive+no_connect"))
    )
    (net (code "61") (name "unconnected-(U301B-NC_B8-PadB8)") (class "Default")
      (node (ref "U301") (pin "B8") (pinfunction "NC_B8_B8") (pintype "passive+no_connect"))
    )
    (net (code "62") (name "unconnected-(U301B-NC_B9-PadB9)") (class "Default")
      (node (ref "U301") (pin "B9") (pinfunction "NC_B9_B9") (pintype "passive+no_connect"))
    )
    (net (code "63") (name "unconnected-(U301B-NC_B10-PadB10)") (class "Default")
      (node (ref "U301") (pin "B10") (pinfunction "NC_B10_B10") (pintype "passive+no_connect"))
    )
    (net (code "64") (name "unconnected-(U301B-NC_B11-PadB11)") (class "Default")
      (node (ref "U301") (pin "B11") (pinfunction "NC_B11_B11") (pintype "passive+no_connect"))
    )
    (net (code "65") (name "unconnected-(U301B-NC_B12-PadB12)") (class "Default")
      (node (ref "U301") (pin "B12") (pinfunction "NC_B12_B12") (pintype "passive+no_connect"))
    )
    (net (code "66") (name "unconnected-(U301B-NC_B13-PadB13)") (class "Default")
      (node (ref "U301") (pin "B13") (pinfunction "NC_B13_B13") (pintype "passive+no_connect"))
    )
    (net (code "67") (name "unconnected-(U301B-NC_B14-PadB14)") (class "Default")
      (node (ref "U301") (pin "B14") (pinfunction "NC_B14_B14") (pintype "passive+no_connect"))
    )
    (net (code "68") (name "unconnected-(U301B-NC_C1-PadC1)") (class "Default")
      (node (ref "U301") (pin "C1") (pinfunction "NC_C1_C1") (pintype "passive+no_connect"))
    )
    (net (code "69") (name "unconnected-(U301B-NC_C3-PadC3)") (class "Default")
      (node (ref "U301") (pin "C3") (pinfunction "NC_C3_C3") (pintype "passive+no_connect"))
    )
    (net (code "70") (name "unconnected-(U301B-NC_C7-PadC7)") (class "Default")
      (node (ref "U301") (pin "C7") (pinfunction "NC_C7_C7") (pintype "passive+no_connect"))
    )
    (net (code "71") (name "unconnected-(U301B-NC_C8-PadC8)") (class "Default")
      (node (ref "U301") (pin "C8") (pinfunction "NC_C8_C8") (pintype "passive+no_connect"))
    )
    (net (code "72") (name "unconnected-(U301B-NC_C9-PadC9)") (class "Default")
      (node (ref "U301") (pin "C9") (pinfunction "NC_C9_C9") (pintype "passive+no_connect"))
    )
    (net (code "73") (name "unconnected-(U301B-NC_C10-PadC10)") (class "Default")
      (node (ref "U301") (pin "C10") (pinfunction "NC_C10_C10") (pintype "passive+no_connect"))
    )
    (net (code "74") (name "unconnected-(U301B-NC_C11-PadC11)") (class "Default")
      (node (ref "U301") (pin "C11") (pinfunction "NC_C11_C11") (pintype "passive+no_connect"))
    )
    (net (code "75") (name "unconnected-(U301B-NC_C12-PadC12)") (class "Default")
      (node (ref "U301") (pin "C12") (pinfunction "NC_C12_C12") (pintype "passive+no_connect"))
    )
    (net (code "76") (name "unconnected-(U301B-NC_C13-PadC13)") (class "Default")
      (node (ref "U301") (pin "C13") (pinfunction "NC_C13_C13") (pintype "passive+no_connect"))
    )
    (net (code "77") (name "unconnected-(U301B-NC_C14-PadC14)") (class "Default")
      (node (ref "U301") (pin "C14") (pinfunction "NC_C14_C14") (pintype "passive+no_connect"))
    )
    (net (code "78") (name "unconnected-(U301B-NC_D1-PadD1)") (class "Default")
      (node (ref "U301") (pin "D1") (pinfunction "NC_D1_D1") (pintype "passive+no_connect"))
    )
    (net (code "79") (name "unconnected-(U301B-NC_D2-PadD2)") (class "Default")
      (node (ref "U301") (pin "D2") (pinfunction "NC_D2_D2") (pintype "passive+no_connect"))
    )
    (net (code "80") (name "unconnected-(U301B-NC_D3-PadD3)") (class "Default")
      (node (ref "U301") (pin "D3") (pinfunction "NC_D3_D3") (pintype "passive+no_connect"))
    )
    (net (code "81") (name "unconnected-(U301B-NC_D4-PadD4)") (class "Default")
      (node (ref "U301") (pin "D4") (pinfunction "NC_D4_D4") (pintype "passive+no_connect"))
    )
    (net (code "82") (name "unconnected-(U301B-NC_D12-PadD12)") (class "Default")
      (node (ref "U301") (pin "D12") (pinfunction "NC_D12_D12") (pintype "passive+no_connect"))
    )
    (net (code "83") (name "unconnected-(U301B-NC_D13-PadD13)") (class "Default")
      (node (ref "U301") (pin "D13") (pinfunction "NC_D13_D13") (pintype "passive+no_connect"))
    )
    (net (code "84") (name "unconnected-(U301B-NC_D14-PadD14)") (class "Default")
      (node (ref "U301") (pin "D14") (pinfunction "NC_D14_D14") (pintype "passive+no_connect"))
    )
    (net (code "85") (name "unconnected-(U301B-NC_E1-PadE1)") (class "Default")
      (node (ref "U301") (pin "E1") (pinfunction "NC_E1_E1") (pintype "passive+no_connect"))
    )
    (net (code "86") (name "unconnected-(U301B-NC_E2-PadE2)") (class "Default")
      (node (ref "U301") (pin "E2") (pinfunction "NC_E2_E2") (pintype "passive+no_connect"))
    )
    (net (code "87") (name "unconnected-(U301B-NC_E3-PadE3)") (class "Default")
      (node (ref "U301") (pin "E3") (pinfunction "NC_E3_E3") (pintype "passive+no_connect"))
    )
    (net (code "88") (name "unconnected-(U301B-NC_E12-PadE12)") (class "Default")
      (node (ref "U301") (pin "E12") (pinfunction "NC_E12_E12") (pintype "passive+no_connect"))
    )
    (net (code "89") (name "unconnected-(U301B-NC_E13-PadE13)") (class "Default")
      (node (ref "U301") (pin "E13") (pinfunction "NC_E13_E13") (pintype "passive+no_connect"))
    )
    (net (code "90") (name "unconnected-(U301B-NC_E14-PadE14)") (class "Default")
      (node (ref "U301") (pin "E14") (pinfunction "NC_E14_E14") (pintype "passive+no_connect"))
    )
    (net (code "91") (name "unconnected-(U301B-NC_F1-PadF1)") (class "Default")
      (node (ref "U301") (pin "F1") (pinfunction "NC_F1_F1") (pintype "passive+no_connect"))
    )
    (net (code "92") (name "unconnected-(U301B-NC_F2-PadF2)") (class "Default")
      (node (ref "U301") (pin "F2") (pinfunction "NC_F2_F2") (pintype "passive+no_connect"))
    )
    (net (code "93") (name "unconnected-(U301B-NC_F3-PadF3)") (class "Default")
      (node (ref "U301") (pin "F3") (pinfunction "NC_F3_F3") (pintype "passive+no_connect"))
    )
    (net (code "94") (name "unconnected-(U301B-NC_F12-PadF12)") (class "Default")
      (node (ref "U301") (pin "F12") (pinfunction "NC_F12_F12") (pintype "passive+no_connect"))
    )
    (net (code "95") (name "unconnected-(U301B-NC_F13-PadF13)") (class "Default")
      (node (ref "U301") (pin "F13") (pinfunction "NC_F13_F13") (pintype "passive+no_connect"))
    )
    (net (code "96") (name "unconnected-(U301B-NC_F14-PadF14)") (class "Default")
      (node (ref "U301") (pin "F14") (pinfunction "NC_F14_F14") (pintype "passive+no_connect"))
    )
    (net (code "97") (name "unconnected-(U301B-NC_G1-PadG1)") (class "Default")
      (node (ref "U301") (pin "G1") (pinfunction "NC_G1_G1") (pintype "passive+no_connect"))
    )
    (net (code "98") (name "unconnected-(U301B-NC_G2-PadG2)") (class "Default")
      (node (ref "U301") (pin "G2") (pinfunction "NC_G2_G2") (pintype "passive+no_connect"))
    )
    (net (code "99") (name "unconnected-(U301B-NC_G12-PadG12)") (class "Default")
      (node (ref "U301") (pin "G12") (pinfunction "NC_G12_G12") (pintype "passive+no_connect"))
    )
    (net (code "100") (name "unconnected-(U301B-NC_G13-PadG13)") (class "Default")
      (node (ref "U301") (pin "G13") (pinfunction "NC_G13_G13") (pintype "passive+no_connect"))
    )
    (net (code "101") (name "unconnected-(U301B-NC_G14-PadG14)") (class "Default")
      (node (ref "U301") (pin "G14") (pinfunction "NC_G14_G14") (pintype "passive+no_connect"))
    )
    (net (code "102") (name "unconnected-(U301B-NC_H1-PadH1)") (class "Default")
      (node (ref "U301") (pin "H1") (pinfunction "NC_H1_H1") (pintype "passive+no_connect"))
    )
    (net (code "103") (name "unconnected-(U301B-NC_H2-PadH2)") (class "Default")
      (node (ref "U301") (pin "H2") (pinfunction "NC_H2_H2") (pintype "passive+no_connect"))
    )
    (net (code "104") (name "unconnected-(U301B-NC_H3-PadH3)") (class "Default")
      (node (ref "U301") (pin "H3") (pinfunction "NC_H3_H3") (pintype "passive+no_connect"))
    )
    (net (code "105") (name "unconnected-(U301B-NC_H12-PadH12)") (class "Default")
      (node (ref "U301") (pin "H12") (pinfunction "NC_H12_H12") (pintype "passive+no_connect"))
    )
    (net (code "106") (name "unconnected-(U301B-NC_H13-PadH13)") (class "Default")
      (node (ref "U301") (pin "H13") (pinfunction "NC_H13_H13") (pintype "passive+no_connect"))
    )
    (net (code "107") (name "unconnected-(U301B-NC_H14-PadH14)") (class "Default")
      (node (ref "U301") (pin "H14") (pinfunction "NC_H14_H14") (pintype "passive+no_connect"))
    )
    (net (code "108") (name "unconnected-(U301B-NC_J1-PadJ1)") (class "Default")
      (node (ref "U301") (pin "J1") (pinfunction "NC_J1_J1") (pintype "passive+no_connect"))
    )
    (net (code "109") (name "unconnected-(U301B-NC_J2-PadJ2)") (class "Default")
      (node (ref "U301") (pin "J2") (pinfunction "NC_J2_J2") (pintype "passive+no_connect"))
    )
    (net (code "110") (name "unconnected-(U301B-NC_J3-PadJ3)") (class "Default")
      (node (ref "U301") (pin "J3") (pinfunction "NC_J3_J3") (pintype "passive+no_connect"))
    )
    (net (code "111") (name "unconnected-(U301B-NC_J12-PadJ12)") (class "Default")
      (node (ref "U301") (pin "J12") (pinfunction "NC_J12_J12") (pintype "passive+no_connect"))
    )
    (net (code "112") (name "unconnected-(U301B-NC_J13-PadJ13)") (class "Default")
      (node (ref "U301") (pin "J13") (pinfunction "NC_J13_J13") (pintype "passive+no_connect"))
    )
    (net (code "113") (name "unconnected-(U301B-NC_J14-PadJ14)") (class "Default")
      (node (ref "U301") (pin "J14") (pinfunction "NC_J14_J14") (pintype "passive+no_connect"))
    )
    (net (code "114") (name "unconnected-(U301B-NC_K1-PadK1)") (class "Default")
      (node (ref "U301") (pin "K1") (pinfunction "NC_K1_K1") (pintype "passive+no_connect"))
    )
    (net (code "115") (name "unconnected-(U301B-NC_K2-PadK2)") (class "Default")
      (node (ref "U301") (pin "K2") (pinfunction "NC_K2_K2") (pintype "passive+no_connect"))
    )
    (net (code "116") (name "unconnected-(U301B-NC_K3-PadK3)") (class "Default")
      (node (ref "U301") (pin "K3") (pinfunction "NC_K3_K3") (pintype "passive+no_connect"))
    )
    (net (code "117") (name "unconnected-(U301B-NC_K12-PadK12)") (class "Default")
      (node (ref "U301") (pin "K12") (pinfunction "NC_K12_K12") (pintype "passive+no_connect"))
    )
    (net (code "118") (name "unconnected-(U301B-NC_K13-PadK13)") (class "Default")
      (node (ref "U301") (pin "K13") (pinfunction "NC_K13_K13") (pintype "passive+no_connect"))
    )
    (net (code "119") (name "unconnected-(U301B-NC_K14-PadK14)") (class "Default")
      (node (ref "U301") (pin "K14") (pinfunction "NC_K14_K14") (pintype "passive+no_connect"))
    )
    (net (code "120") (name "unconnected-(U301B-NC_L1-PadL1)") (class "Default")
      (node (ref "U301") (pin "L1") (pinfunction "NC_L1_L1") (pintype "passive+no_connect"))
    )
    (net (code "121") (name "unconnected-(U301B-NC_L2-PadL2)") (class "Default")
      (node (ref "U301") (pin "L2") (pinfunction "NC_L2_L2") (pintype "passive+no_connect"))
    )
    (net (code "122") (name "unconnected-(U301B-NC_L3-PadL3)") (class "Default")
      (node (ref "U301") (pin "L3") (pinfunction "NC_L3_L3") (pintype "passive+no_connect"))
    )
    (net (code "123") (name "unconnected-(U301B-NC_L12-PadL12)") (class "Default")
      (node (ref "U301") (pin "L12") (pinfunction "NC_L12_L12") (pintype "passive+no_connect"))
    )
    (net (code "124") (name "unconnected-(U301B-NC_L13-PadL13)") (class "Default")
      (node (ref "U301") (pin "L13") (pinfunction "NC_L13_L13") (pintype "passive+no_connect"))
    )
    (net (code "125") (name "unconnected-(U301B-NC_L14-PadL14)") (class "Default")
      (node (ref "U301") (pin "L14") (pinfunction "NC_L14_L14") (pintype "passive+no_connect"))
    )
    (net (code "126") (name "unconnected-(U301B-NC_M1-PadM1)") (class "Default")
      (node (ref "U301") (pin "M1") (pinfunction "NC_M1_M1") (pintype "passive+no_connect"))
    )
    (net (code "127") (name "unconnected-(U301B-NC_M2-PadM2)") (class "Default")
      (node (ref "U301") (pin "M2") (pinfunction "NC_M2_M2") (pintype "passive+no_connect"))
    )
    (net (code "128") (name "unconnected-(U301B-NC_M3-PadM3)") (class "Default")
      (node (ref "U301") (pin "M3") (pinfunction "NC_M3_M3") (pintype "passive+no_connect"))
    )
    (net (code "129") (name "unconnected-(U301B-NC_M7-PadM7)") (class "Default")
      (node (ref "U301") (pin "M7") (pinfunction "NC_M7_M7") (pintype "passive+no_connect"))
    )
    (net (code "130") (name "unconnected-(U301B-NC_M8-PadM8)") (class "Default")
      (node (ref "U301") (pin "M8") (pinfunction "NC_M8_M8") (pintype "passive+no_connect"))
    )
    (net (code "131") (name "unconnected-(U301B-NC_M9-PadM9)") (class "Default")
      (node (ref "U301") (pin "M9") (pinfunction "NC_M9_M9") (pintype "passive+no_connect"))
    )
    (net (code "132") (name "unconnected-(U301B-NC_M10-PadM10)") (class "Default")
      (node (ref "U301") (pin "M10") (pinfunction "NC_M10_M10") (pintype "passive+no_connect"))
    )
    (net (code "133") (name "unconnected-(U301B-NC_M11-PadM11)") (class "Default")
      (node (ref "U301") (pin "M11") (pinfunction "NC_M11_M11") (pintype "passive+no_connect"))
    )
    (net (code "134") (name "unconnected-(U301B-NC_M12-PadM12)") (class "Default")
      (node (ref "U301") (pin "M12") (pinfunction "NC_M12_M12") (pintype "passive+no_connect"))
    )
    (net (code "135") (name "unconnected-(U301B-NC_M13-PadM13)") (class "Default")
      (node (ref "U301") (pin "M13") (pinfunction "NC_M13_M13") (pintype "passive+no_connect"))
    )
    (net (code "136") (name "unconnected-(U301B-NC_M14-PadM14)") (class "Default")
      (node (ref "U301") (pin "M14") (pinfunction "NC_M14_M14") (pintype "passive+no_connect"))
    )
    (net (code "137") (name "unconnected-(U301B-NC_N1-PadN1)") (class "Default")
      (node (ref "U301") (pin "N1") (pinfunction "NC_N1_N1") (pintype "passive+no_connect"))
    )
    (net (code "138") (name "unconnected-(U301B-NC_N3-PadN3)") (class "Default")
      (node (ref "U301") (pin "N3") (pinfunction "NC_N3_N3") (pintype "passive+no_connect"))
    )
    (net (code "139") (name "unconnected-(U301B-NC_N6-PadN6)") (class "Default")
      (node (ref "U301") (pin "N6") (pinfunction "NC_N6_N6") (pintype "passive+no_connect"))
    )
    (net (code "140") (name "unconnected-(U301B-NC_N7-PadN7)") (class "Default")
      (node (ref "U301") (pin "N7") (pinfunction "NC_N7_N7") (pintype "passive+no_connect"))
    )
    (net (code "141") (name "unconnected-(U301B-NC_N8-PadN8)") (class "Default")
      (node (ref "U301") (pin "N8") (pinfunction "NC_N8_N8") (pintype "passive+no_connect"))
    )
    (net (code "142") (name "unconnected-(U301B-NC_N9-PadN9)") (class "Default")
      (node (ref "U301") (pin "N9") (pinfunction "NC_N9_N9") (pintype "passive+no_connect"))
    )
    (net (code "143") (name "unconnected-(U301B-NC_N10-PadN10)") (class "Default")
      (node (ref "U301") (pin "N10") (pinfunction "NC_N10_N10") (pintype "passive+no_connect"))
    )
    (net (code "144") (name "unconnected-(U301B-NC_N11-PadN11)") (class "Default")
      (node (ref "U301") (pin "N11") (pinfunction "NC_N11_N11") (pintype "passive+no_connect"))
    )
    (net (code "145") (name "unconnected-(U301B-NC_N12-PadN12)") (class "Default")
      (node (ref "U301") (pin "N12") (pinfunction "NC_N12_N12") (pintype "passive+no_connect"))
    )
    (net (code "146") (name "unconnected-(U301B-NC_N13-PadN13)") (class "Default")
      (node (ref "U301") (pin "N13") (pinfunction "NC_N13_N13") (pintype "passive+no_connect"))
    )
    (net (code "147") (name "unconnected-(U301B-NC_N14-PadN14)") (class "Default")
      (node (ref "U301") (pin "N14") (pinfunction "NC_N14_N14") (pintype "passive+no_connect"))
    )
    (net (code "148") (name "unconnected-(U301B-NC_P1-PadP1)") (class "Default")
      (node (ref "U301") (pin "P1") (pinfunction "NC_P1_P1") (pintype "passive+no_connect"))
    )
    (net (code "149") (name "unconnected-(U301B-NC_P2-PadP2)") (class "Default")
      (node (ref "U301") (pin "P2") (pinfunction "NC_P2_P2") (pintype "passive+no_connect"))
    )
    (net (code "150") (name "unconnected-(U301B-NC_P8-PadP8)") (class "Default")
      (node (ref "U301") (pin "P8") (pinfunction "NC_P8_P8") (pintype "passive+no_connect"))
    )
    (net (code "151") (name "unconnected-(U301B-NC_P9-PadP9)") (class "Default")
      (node (ref "U301") (pin "P9") (pinfunction "NC_P9_P9") (pintype "passive+no_connect"))
    )
    (net (code "152") (name "unconnected-(U301B-NC_P11-PadP11)") (class "Default")
      (node (ref "U301") (pin "P11") (pinfunction "NC_P11_P11") (pintype "passive+no_connect"))
    )
    (net (code "153") (name "unconnected-(U301B-NC_P12-PadP12)") (class "Default")
      (node (ref "U301") (pin "P12") (pinfunction "NC_P12_P12") (pintype "passive+no_connect"))
    )
    (net (code "154") (name "unconnected-(U301B-NC_P13-PadP13)") (class "Default")
      (node (ref "U301") (pin "P13") (pinfunction "NC_P13_P13") (pintype "passive+no_connect"))
    )
    (net (code "155") (name "unconnected-(U301B-NC_P14-PadP14)") (class "Default")
      (node (ref "U301") (pin "P14") (pinfunction "NC_P14_P14") (pintype "passive+no_connect"))
    )
    (net (code "156") (name "unconnected-(U301B-RFU2-PadA7)") (class "Default")
      (node (ref "U301") (pin "A7") (pinfunction "RFU2_A7") (pintype "passive+no_connect"))
    )
    (net (code "157") (name "unconnected-(U301B-RFU3-PadC5)") (class "Default")
      (node (ref "U301") (pin "C5") (pinfunction "RFU3_C5") (pintype "passive+no_connect"))
    )
    (net (code "158") (name "unconnected-(U301B-RFU4-PadE10)") (class "Default")
      (node (ref "U301") (pin "E10") (pinfunction "RFU4_E10") (pintype "passive+no_connect"))
    )
    (net (code "159") (name "unconnected-(U301B-RFU5-PadE5)") (class "Default")
      (node (ref "U301") (pin "E5") (pinfunction "RFU5_E5") (pintype "passive+no_connect"))
    )
    (net (code "160") (name "unconnected-(U301B-RFU6-PadE8)") (class "Default")
      (node (ref "U301") (pin "E8") (pinfunction "RFU6_E8") (pintype "passive+no_connect"))
    )
    (net (code "161") (name "unconnected-(U301B-RFU7-PadE9)") (class "Default")
      (node (ref "U301") (pin "E9") (pinfunction "RFU7_E9") (pintype "passive+no_connect"))
    )
    (net (code "162") (name "unconnected-(U301B-RFU8-PadF10)") (class "Default")
      (node (ref "U301") (pin "F10") (pinfunction "RFU8_F10") (pintype "passive+no_connect"))
    )
    (net (code "163") (name "unconnected-(U301B-RFU9-PadG10)") (class "Default")
      (node (ref "U301") (pin "G10") (pinfunction "RFU9_G10") (pintype "passive+no_connect"))
    )
    (net (code "164") (name "unconnected-(U301B-RFU10-PadG3)") (class "Default")
      (node (ref "U301") (pin "G3") (pinfunction "RFU10_G3") (pintype "passive+no_connect"))
    )
    (net (code "165") (name "unconnected-(U301B-RFU11-PadH5)") (class "Default")
      (node (ref "U301") (pin "H5") (pinfunction "RFU11_H5") (pintype "passive+no_connect"))
    )
    (net (code "166") (name "unconnected-(U301B-RFU13-PadK10)") (class "Default")
      (node (ref "U301") (pin "K10") (pinfunction "RFU13_K10") (pintype "passive+no_connect"))
    )
    (net (code "167") (name "unconnected-(U301B-RFU14-PadK6)") (class "Default")
      (node (ref "U301") (pin "K6") (pinfunction "RFU14_K6") (pintype "passive+no_connect"))
    )
    (net (code "168") (name "unconnected-(U301B-RFU15-PadK7)") (class "Default")
      (node (ref "U301") (pin "K7") (pinfunction "RFU15_K7") (pintype "passive+no_connect"))
    )
    (net (code "169") (name "unconnected-(U301B-RFU16-PadP10)") (class "Default")
      (node (ref "U301") (pin "P10") (pinfunction "RFU16_P10") (pintype "passive+no_connect"))
    )
    (net (code "170") (name "unconnected-(U301B-RFU17-PadP7)") (class "Default")
      (node (ref "U301") (pin "P7") (pinfunction "RFU17_P7") (pintype "passive+no_connect"))
    )
    (net (code "171") (name "unconnected-(U302-DNU_1-Pad20)") (class "Default")
      (node (ref "U302") (pin "20") (pinfunction "DNU_1_20") (pintype "passive+no_connect"))
    )
    (net (code "172") (name "unconnected-(U302-DNU_2-Pad21)") (class "Default")
      (node (ref "U302") (pin "21") (pinfunction "DNU_2_21") (pintype "passive+no_connect"))
    )
    (net (code "173") (name "unconnected-(U302-DNU_4-Pad38)") (class "Default")
      (node (ref "U302") (pin "38") (pinfunction "DNU_4_38") (pintype "passive+no_connect"))
    )
    (net (code "174") (name "unconnected-(U302-NC_1-Pad1)") (class "Default")
      (node (ref "U302") (pin "1") (pinfunction "NC_1_1") (pintype "passive+no_connect"))
    )
    (net (code "175") (name "unconnected-(U302-NC_2-Pad2)") (class "Default")
      (node (ref "U302") (pin "2") (pinfunction "NC_2_2") (pintype "passive+no_connect"))
    )
    (net (code "176") (name "unconnected-(U302-NC_3-Pad3)") (class "Default")
      (node (ref "U302") (pin "3") (pinfunction "NC_3_3") (pintype "passive+no_connect"))
    )
    (net (code "177") (name "unconnected-(U302-NC_11-Pad11)") (class "Default")
      (node (ref "U302") (pin "11") (pinfunction "NC_11_11") (pintype "passive+no_connect"))
    )
    (net (code "178") (name "unconnected-(U302-NC_22-Pad22)") (class "Default")
      (node (ref "U302") (pin "22") (pinfunction "NC_22_22") (pintype "passive+no_connect"))
    )
    (net (code "179") (name "unconnected-(U302-NC_23-Pad23)") (class "Default")
      (node (ref "U302") (pin "23") (pinfunction "NC_23_23") (pintype "passive+no_connect"))
    )
    (net (code "180") (name "unconnected-(U302-NC_24-Pad24)") (class "Default")
      (node (ref "U302") (pin "24") (pinfunction "NC_24_24") (pintype "passive+no_connect"))
    )
    (net (code "181") (name "unconnected-(U302-NC_26-Pad26)") (class "Default")
      (node (ref "U302") (pin "26") (pinfunction "NC_26_26") (pintype "passive+no_connect"))
    )
    (net (code "182") (name "unconnected-(U302-NC_27-Pad27)") (class "Default")
      (node (ref "U302") (pin "27") (pinfunction "NC_27_27") (pintype "passive+no_connect"))
    )
    (net (code "183") (name "unconnected-(U302-NC_28-Pad28)") (class "Default")
      (node (ref "U302") (pin "28") (pinfunction "NC_28_28") (pintype "passive+no_connect"))
    )
    (net (code "184") (name "unconnected-(U302-NC_33-Pad33)") (class "Default")
      (node (ref "U302") (pin "33") (pinfunction "NC_33_33") (pintype "passive+no_connect"))
    )
    (net (code "185") (name "unconnected-(U302-NC_40-Pad40)") (class "Default")
      (node (ref "U302") (pin "40") (pinfunction "NC_40_40") (pintype "passive+no_connect"))
    )
    (net (code "186") (name "unconnected-(U302-NC_45-Pad45)") (class "Default")
      (node (ref "U302") (pin "45") (pinfunction "NC_45_45") (pintype "passive+no_connect"))
    )
    (net (code "187") (name "unconnected-(U302-NC_46-Pad46)") (class "Default")
      (node (ref "U302") (pin "46") (pinfunction "NC_46_46") (pintype "passive+no_connect"))
    )
    (net (code "188") (name "unconnected-(U302-NC_47-Pad47)") (class "Default")
      (node (ref "U302") (pin "47") (pinfunction "NC_47_47") (pintype "passive+no_connect"))
    )
  )
)
